# TS-ARM3_0_5.net
KiCad netlist of a schematic drawn in EAGLE
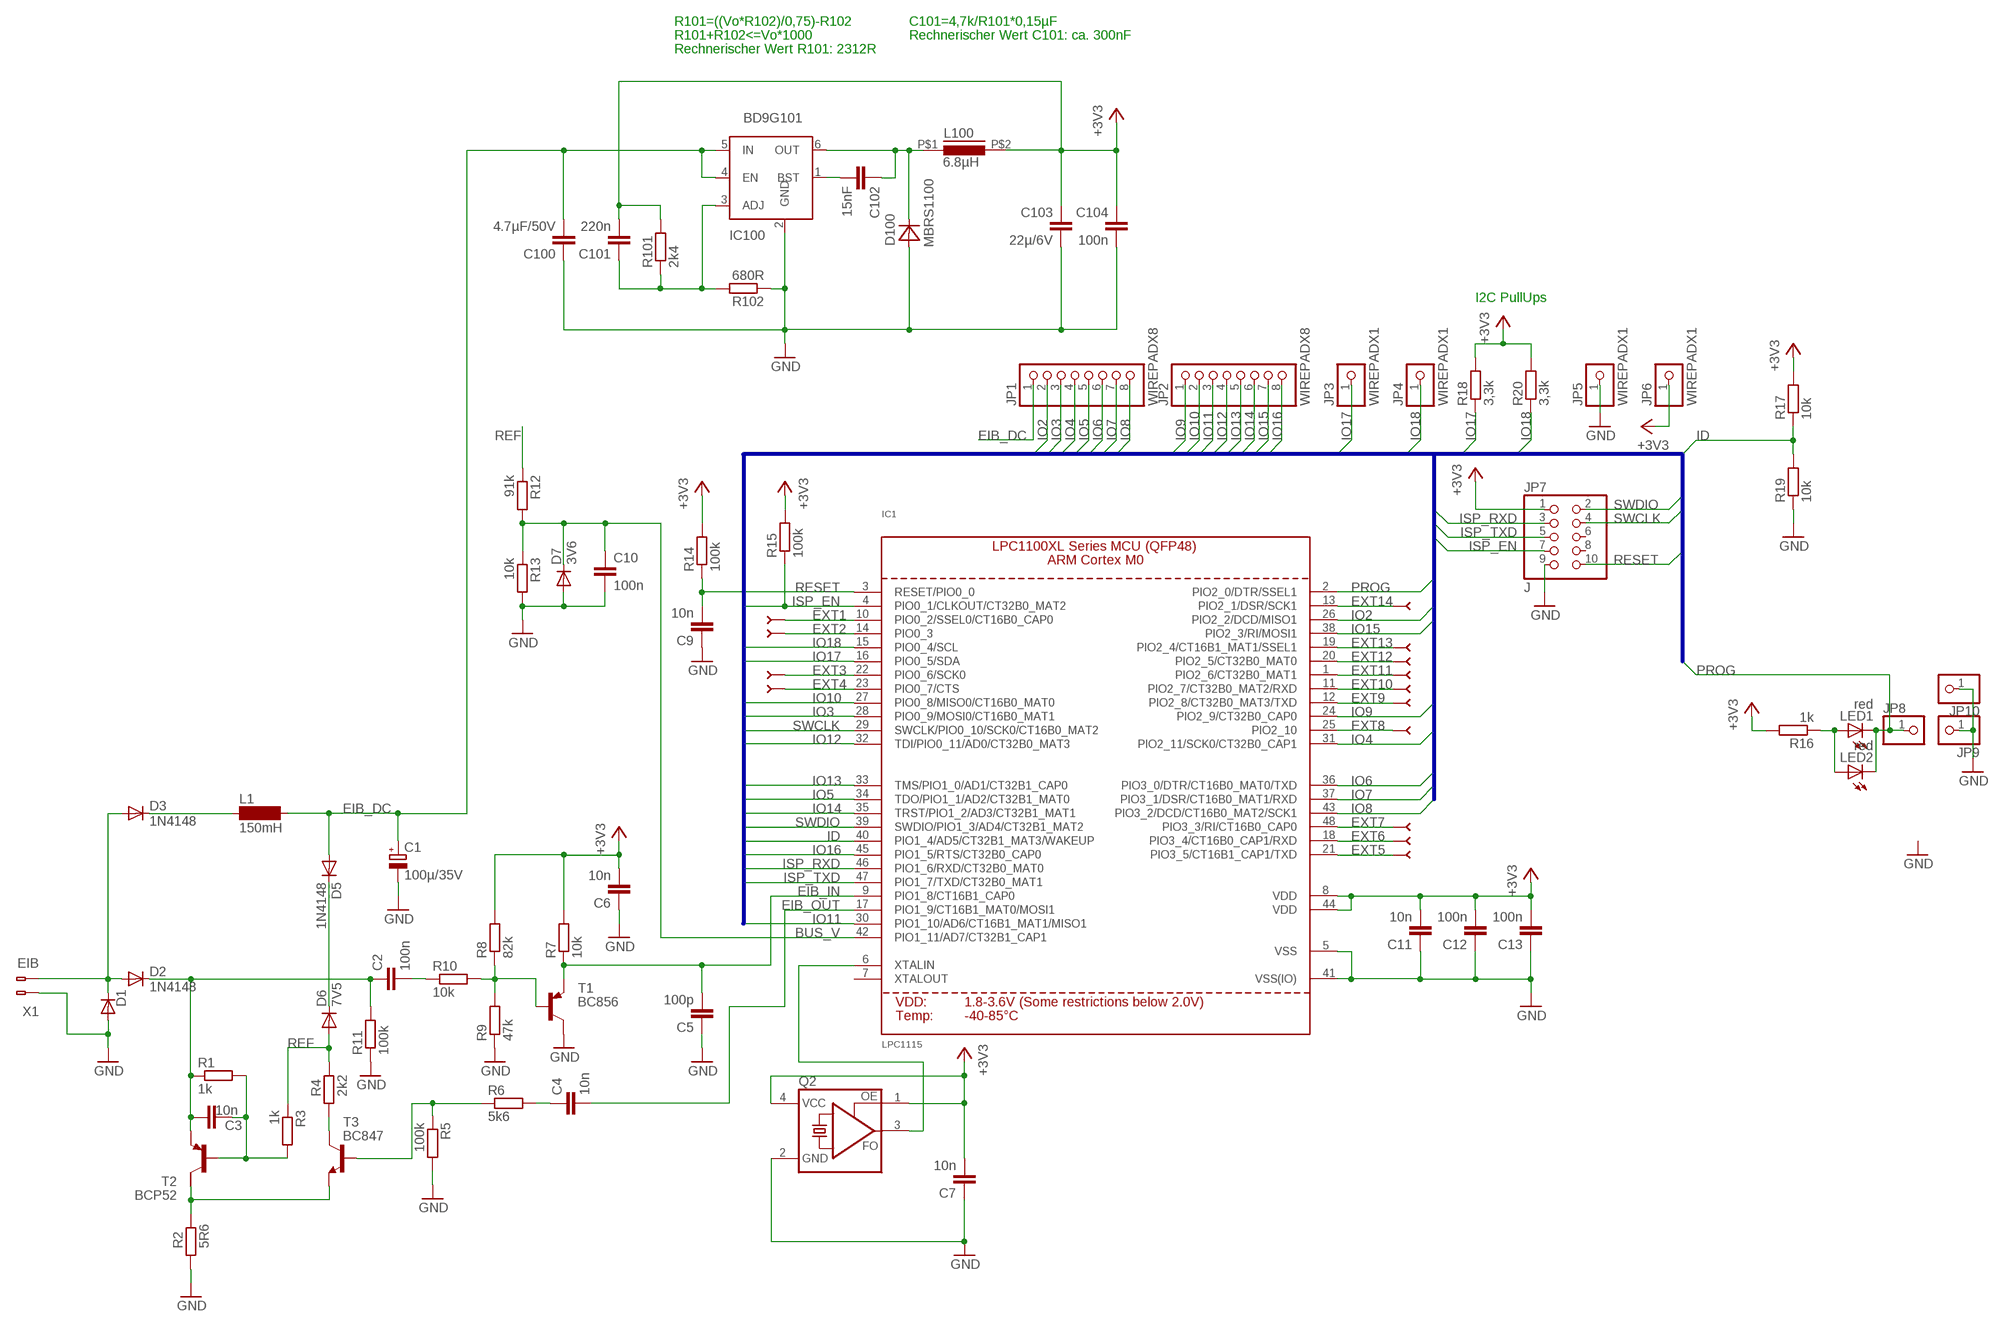
[diagram p0: schematic, sheet 1]

(export (version "E")
  (design (tool "Eeschema 10.0.6"))
  (components
    (comp (ref "C1")
      (value "100µ/35V")
      (footprint "eagle-import:SANYO-OSCON_SMD_C6")
      (libsource (lib "eagle-import") (part "CPOL-EUSANYO_SMD_C6"))
    )
    (comp (ref "C2")
      (value "100n")
      (footprint "eagle-import:C1206")
      (libsource (lib "eagle-import") (part "C-EUC1206"))
    )
    (comp (ref "C3")
      (value "10n")
      (footprint "eagle-import:C1206")
      (libsource (lib "eagle-import") (part "C-EUC1206"))
    )
    (comp (ref "C4")
      (value "10n")
      (footprint "eagle-import:C1206")
      (libsource (lib "eagle-import") (part "C-EUC1206"))
    )
    (comp (ref "C5")
      (value "100p")
      (footprint "eagle-import:C1206")
      (libsource (lib "eagle-import") (part "C-EUC1206"))
    )
    (comp (ref "C6")
      (value "10n")
      (footprint "eagle-import:C1206")
      (libsource (lib "eagle-import") (part "C-EUC1206"))
    )
    (comp (ref "C7")
      (value "10n")
      (footprint "eagle-import:C1206")
      (libsource (lib "eagle-import") (part "C-EUC1206"))
    )
    (comp (ref "C9")
      (value "10n")
      (footprint "eagle-import:C1206")
      (libsource (lib "eagle-import") (part "C-EUC1206"))
    )
    (comp (ref "C10")
      (value "100n")
      (footprint "eagle-import:C1206")
      (libsource (lib "eagle-import") (part "C-EUC1206"))
    )
    (comp (ref "C11")
      (value "10n")
      (footprint "eagle-import:C1206")
      (libsource (lib "eagle-import") (part "C-EUC1206"))
    )
    (comp (ref "C12")
      (value "100n")
      (footprint "eagle-import:C1206")
      (libsource (lib "eagle-import") (part "C-EUC1206"))
    )
    (comp (ref "C13")
      (value "100n")
      (footprint "eagle-import:C1206")
      (libsource (lib "eagle-import") (part "C-EUC1206"))
    )
    (comp (ref "C100")
      (value "4.7µF/50V")
      (footprint "eagle-import:C1206")
      (libsource (lib "eagle-import") (part "C-EUC1206"))
    )
    (comp (ref "C101")
      (value "220n")
      (footprint "eagle-import:C1206")
      (libsource (lib "eagle-import") (part "C-EUC1206"))
    )
    (comp (ref "C102")
      (value "15nF")
      (footprint "eagle-import:C1206")
      (libsource (lib "eagle-import") (part "C-EUC1206"))
    )
    (comp (ref "C103")
      (value "22µ/6V")
      (footprint "eagle-import:C1206")
      (libsource (lib "eagle-import") (part "C-EUC1206"))
    )
    (comp (ref "C104")
      (value "100n")
      (footprint "eagle-import:C1206")
      (libsource (lib "eagle-import") (part "C-EUC1206"))
    )
    (comp (ref "D1")
      (value "SMAJ40C")
      (footprint "eagle-import:SMB")
      (libsource (lib "eagle-import") (part "D-SMB"))
    )
    (comp (ref "D2")
      (value "1N4148")
      (footprint "eagle-import:MINIMELF")
      (libsource (lib "eagle-import") (part "DIODE-MINIMELF"))
    )
    (comp (ref "D3")
      (value "1N4148")
      (footprint "eagle-import:MINIMELF")
      (libsource (lib "eagle-import") (part "DIODE-MINIMELF"))
    )
    (comp (ref "D5")
      (value "1N4148")
      (footprint "eagle-import:MINIMELF")
      (libsource (lib "eagle-import") (part "DIODE-MINIMELF"))
    )
    (comp (ref "D6")
      (value "7V5")
      (footprint "eagle-import:MINIMELF")
      (libsource (lib "eagle-import") (part "DIODE-MINIMELF"))
    )
    (comp (ref "D7")
      (value "3V6")
      (footprint "eagle-import:MINIMELF")
      (libsource (lib "eagle-import") (part "DIODE-MINIMELF"))
    )
    (comp (ref "D100")
      (value "MBRS1100")
      (footprint "eagle-import:SMA")
      (libsource (lib "eagle-import") (part "MBRA340T3"))
    )
    (comp (ref "IC1")
      (value "LPC1115")
      (footprint "eagle-import:LQFP48")
      (libsource (lib "eagle-import") (part "LPC1113/4/5_QFP48_XLSERIES"))
    )
    (comp (ref "IC100")
      (value "BD9G101")
      (footprint "eagle-import:SOT23-6")
      (libsource (lib "eagle-import") (part "BD9G101GBD9G101G-SOT23-6"))
    )
    (comp (ref "JP1")
      (value "WIREPADX8")
      (footprint "eagle-import:SMD1,27X2,54X8")
      (libsource (lib "eagle-import") (part "WIREPADX8"))
    )
    (comp (ref "JP2")
      (value "WIREPADX8")
      (footprint "eagle-import:SMD1,27X2,54X8")
      (libsource (lib "eagle-import") (part "WIREPADX8"))
    )
    (comp (ref "JP3")
      (value "WIREPADX1")
      (footprint "eagle-import:SMD1,27X2,54")
      (libsource (lib "eagle-import") (part "WIREPADX1"))
    )
    (comp (ref "JP4")
      (value "WIREPADX1")
      (footprint "eagle-import:SMD1,27X2,54")
      (libsource (lib "eagle-import") (part "WIREPADX1"))
    )
    (comp (ref "JP5")
      (value "WIREPADX1")
      (footprint "eagle-import:SMD1,27X2,54")
      (libsource (lib "eagle-import") (part "WIREPADX1"))
    )
    (comp (ref "JP6")
      (value "WIREPADX1")
      (footprint "eagle-import:SMD1,27X2,54")
      (libsource (lib "eagle-import") (part "WIREPADX1"))
    )
    (comp (ref "JP7")
      (value "J")
      (footprint "eagle-import:2X05M")
      (libsource (lib "eagle-import") (part "PINHD-2X05_2.00"))
    )
    (comp (ref "JP8")
      (value "PINHD-1X1")
      (footprint "eagle-import:1X01")
      (libsource (lib "eagle-import") (part "PINHD-1X1"))
    )
    (comp (ref "JP9")
      (value "PINHD-1X1")
      (footprint "eagle-import:1X01")
      (libsource (lib "eagle-import") (part "PINHD-1X1"))
    )
    (comp (ref "JP10")
      (value "PINHD-1X1")
      (footprint "eagle-import:1X01")
      (libsource (lib "eagle-import") (part "PINHD-1X1"))
    )
    (comp (ref "L1")
      (value "150mH")
      (footprint "eagle-import:SD12_1000")
      (libsource (lib "eagle-import") (part "SD12-1000"))
    )
    (comp (ref "L100")
      (value "6.8µH")
      (footprint "eagle-import:PIS2812")
      (libsource (lib "eagle-import") (part "IND_FASTRON_1616FPS"))
    )
    (comp (ref "LED1")
      (value "red")
      (footprint "eagle-import:CHIPLED_1206")
      (libsource (lib "eagle-import") (part "LEDCHIPLED_1206"))
    )
    (comp (ref "LED2")
      (value "red")
      (footprint "eagle-import:LED3MM")
      (libsource (lib "eagle-import") (part "LED3MM"))
    )
    (comp (ref "P1")
      (value "PAD")
      (footprint "eagle-import:PAD")
      (libsource (lib "eagle-import") (part "PAD"))
    )
    (comp (ref "P2")
      (value "PAD")
      (footprint "eagle-import:PAD")
      (libsource (lib "eagle-import") (part "PAD"))
    )
    (comp (ref "P3")
      (value "PAD")
      (footprint "eagle-import:PAD")
      (libsource (lib "eagle-import") (part "PAD"))
    )
    (comp (ref "P4")
      (value "PAD")
      (footprint "eagle-import:PAD")
      (libsource (lib "eagle-import") (part "PAD"))
    )
    (comp (ref "P5")
      (value "PAD")
      (footprint "eagle-import:PAD")
      (libsource (lib "eagle-import") (part "PAD"))
    )
    (comp (ref "P6")
      (value "PAD")
      (footprint "eagle-import:PAD")
      (libsource (lib "eagle-import") (part "PAD"))
    )
    (comp (ref "P7")
      (value "PAD")
      (footprint "eagle-import:PAD")
      (libsource (lib "eagle-import") (part "PAD"))
    )
    (comp (ref "P8")
      (value "PAD")
      (footprint "eagle-import:PAD")
      (libsource (lib "eagle-import") (part "PAD"))
    )
    (comp (ref "P9")
      (value "PAD")
      (footprint "eagle-import:PAD")
      (libsource (lib "eagle-import") (part "PAD"))
    )
    (comp (ref "P10")
      (value "PAD")
      (footprint "eagle-import:PAD")
      (libsource (lib "eagle-import") (part "PAD"))
    )
    (comp (ref "P11")
      (value "PAD")
      (footprint "eagle-import:PAD")
      (libsource (lib "eagle-import") (part "PAD"))
    )
    (comp (ref "P12")
      (value "PAD")
      (footprint "eagle-import:PAD")
      (libsource (lib "eagle-import") (part "PAD"))
    )
    (comp (ref "P13")
      (value "PAD")
      (footprint "eagle-import:PAD")
      (libsource (lib "eagle-import") (part "PAD"))
    )
    (comp (ref "P14")
      (value "PAD")
      (footprint "eagle-import:PAD")
      (libsource (lib "eagle-import") (part "PAD"))
    )
    (comp (ref "Q2")
      (value "ASFL")
      (footprint "eagle-import:ASF")
      (libsource (lib "eagle-import") (part "ASFL"))
    )
    (comp (ref "R1")
      (value "1k")
      (footprint "eagle-import:R1206")
      (libsource (lib "eagle-import") (part "R-EU_R1206"))
    )
    (comp (ref "R2")
      (value "5R6")
      (footprint "eagle-import:R1206")
      (libsource (lib "eagle-import") (part "R-EU_R1206"))
    )
    (comp (ref "R3")
      (value "1k")
      (footprint "eagle-import:R1206")
      (libsource (lib "eagle-import") (part "R-EU_R1206"))
    )
    (comp (ref "R4")
      (value "2k2")
      (footprint "eagle-import:R1206")
      (libsource (lib "eagle-import") (part "R-EU_R1206"))
    )
    (comp (ref "R5")
      (value "100k")
      (footprint "eagle-import:R1206")
      (libsource (lib "eagle-import") (part "R-EU_R1206"))
    )
    (comp (ref "R6")
      (value "5k6")
      (footprint "eagle-import:R1206")
      (libsource (lib "eagle-import") (part "R-EU_R1206"))
    )
    (comp (ref "R7")
      (value "10k")
      (footprint "eagle-import:R1206")
      (libsource (lib "eagle-import") (part "R-EU_R1206"))
    )
    (comp (ref "R8")
      (value "82k")
      (footprint "eagle-import:R1206")
      (libsource (lib "eagle-import") (part "R-EU_R1206"))
    )
    (comp (ref "R9")
      (value "47k")
      (footprint "eagle-import:R1206")
      (libsource (lib "eagle-import") (part "R-EU_R1206"))
    )
    (comp (ref "R10")
      (value "10k")
      (footprint "eagle-import:R1206")
      (libsource (lib "eagle-import") (part "R-EU_R1206"))
    )
    (comp (ref "R11")
      (value "100k")
      (footprint "eagle-import:R1206")
      (libsource (lib "eagle-import") (part "R-EU_R1206"))
    )
    (comp (ref "R12")
      (value "91k")
      (footprint "eagle-import:R1206")
      (libsource (lib "eagle-import") (part "R-EU_R1206"))
    )
    (comp (ref "R13")
      (value "10k")
      (footprint "eagle-import:R1206")
      (libsource (lib "eagle-import") (part "R-EU_R1206"))
    )
    (comp (ref "R14")
      (value "100k")
      (footprint "eagle-import:R1206")
      (libsource (lib "eagle-import") (part "R-EU_R1206"))
    )
    (comp (ref "R15")
      (value "100k")
      (footprint "eagle-import:R1206")
      (libsource (lib "eagle-import") (part "R-EU_R1206"))
    )
    (comp (ref "R16")
      (value "1k")
      (footprint "eagle-import:R1206")
      (libsource (lib "eagle-import") (part "R-EU_R1206"))
    )
    (comp (ref "R17")
      (value "10k")
      (footprint "eagle-import:R1206")
      (libsource (lib "eagle-import") (part "R-EU_R1206"))
    )
    (comp (ref "R18")
      (value "3,3k")
      (footprint "eagle-import:R1206")
      (libsource (lib "eagle-import") (part "R-EU_R1206"))
    )
    (comp (ref "R19")
      (value "10k")
      (footprint "eagle-import:R1206")
      (libsource (lib "eagle-import") (part "R-EU_R1206"))
    )
    (comp (ref "R20")
      (value "3,3k")
      (footprint "eagle-import:R1206")
      (libsource (lib "eagle-import") (part "R-EU_R1206"))
    )
    (comp (ref "R101")
      (value "2k4")
      (footprint "eagle-import:R1206")
      (libsource (lib "eagle-import") (part "R-EU_R1206"))
    )
    (comp (ref "R102")
      (value "680R")
      (footprint "eagle-import:R1206")
      (libsource (lib "eagle-import") (part "R-EU_R1206"))
    )
    (comp (ref "T1")
      (value "BC856")
      (footprint "eagle-import:SOT23-BEC")
      (libsource (lib "eagle-import") (part "BC856SMDB"))
    )
    (comp (ref "T2")
      (value "BCP52")
      (footprint "eagle-import:SOT223")
      (libsource (lib "eagle-import") (part "FZT753SMD"))
    )
    (comp (ref "T3")
      (value "BC847")
      (footprint "eagle-import:SOT23")
      (libsource (lib "eagle-import") (part "BC847"))
    )
    (comp (ref "X1")
      (value "EIB")
      (footprint "eagle-import:BUSKLEMME243-724")
      (libsource (lib "eagle-import") (part "EIB"))
    )
  )
  (nets
    (net (code "1") (name "+3V3") (class "Default")
      (node (ref "C101") (pin "2") (pinfunction "2_2") (pintype "passive"))
      (node (ref "C103") (pin "1") (pinfunction "1_1") (pintype "passive"))
      (node (ref "C104") (pin "1") (pinfunction "1_1") (pintype "passive"))
      (node (ref "C11") (pin "2") (pinfunction "2_2") (pintype "passive"))
      (node (ref "C12") (pin "2") (pinfunction "2_2") (pintype "passive"))
      (node (ref "C13") (pin "2") (pinfunction "2_2") (pintype "passive"))
      (node (ref "C6") (pin "2") (pinfunction "2_2") (pintype "passive"))
      (node (ref "C7") (pin "2") (pinfunction "2_2") (pintype "passive"))
      (node (ref "IC1") (pin "44") (pinfunction "VDD_44") (pintype "power_in"))
      (node (ref "IC1") (pin "8") (pinfunction "VDD_8") (pintype "power_in"))
      (node (ref "JP6") (pin "1") (pinfunction "1_1") (pintype "passive"))
      (node (ref "JP7") (pin "1") (pinfunction "1_1") (pintype "passive"))
      (node (ref "L100") (pin "P$2") (pinfunction "2_P$2") (pintype "passive"))
      (node (ref "Q2") (pin "1") (pinfunction "OE_1") (pintype "input"))
      (node (ref "Q2") (pin "4") (pinfunction "VCC_4") (pintype "power_in"))
      (node (ref "R101") (pin "2") (pinfunction "2_2") (pintype "passive"))
      (node (ref "R14") (pin "2") (pinfunction "2_2") (pintype "passive"))
      (node (ref "R15") (pin "2") (pinfunction "2_2") (pintype "passive"))
      (node (ref "R16") (pin "2") (pinfunction "2_2") (pintype "passive"))
      (node (ref "R17") (pin "2") (pinfunction "2_2") (pintype "passive"))
      (node (ref "R18") (pin "2") (pinfunction "2_2") (pintype "passive"))
      (node (ref "R20") (pin "2") (pinfunction "2_2") (pintype "passive"))
      (node (ref "R7") (pin "2") (pinfunction "2_2") (pintype "passive"))
      (node (ref "R8") (pin "2") (pinfunction "2_2") (pintype "passive"))
    )
    (net (code "2") (name "/BUS_V") (class "Default")
      (node (ref "C10") (pin "2") (pinfunction "2_2") (pintype "passive"))
      (node (ref "D7") (pin "C") (pinfunction "C_C") (pintype "passive"))
      (node (ref "IC1") (pin "42") (pinfunction "PIO1_11/AD7/CT32B1_CAP1_42") (pintype "bidirectional"))
      (node (ref "R12") (pin "2") (pinfunction "2_2") (pintype "passive"))
      (node (ref "R13") (pin "1") (pinfunction "1_1") (pintype "passive"))
    )
    (net (code "3") (name "/EIB_DC") (class "Default")
      (node (ref "C1") (pin "+") (pinfunction "+_+") (pintype "passive"))
      (node (ref "C100") (pin "2") (pinfunction "2_2") (pintype "passive"))
      (node (ref "D5") (pin "A") (pinfunction "A_A") (pintype "passive"))
      (node (ref "IC100") (pin "4") (pinfunction "EN_4") (pintype "input"))
      (node (ref "IC100") (pin "5") (pinfunction "IN_5") (pintype "input"))
      (node (ref "JP1") (pin "1") (pinfunction "1_1") (pintype "passive"))
      (node (ref "L1") (pin "2") (pinfunction "2_2") (pintype "passive"))
    )
    (net (code "4") (name "/EIB_IN") (class "Default")
      (node (ref "C5") (pin "2") (pinfunction "2_2") (pintype "passive"))
      (node (ref "IC1") (pin "9") (pinfunction "PIO1_8/CT16B1_CAP0_9") (pintype "bidirectional"))
      (node (ref "R7") (pin "1") (pinfunction "1_1") (pintype "passive"))
      (node (ref "T1") (pin "E") (pinfunction "E_E") (pintype "passive"))
    )
    (net (code "5") (name "/EIB_OUT") (class "Default")
      (node (ref "C4") (pin "2") (pinfunction "2_2") (pintype "passive"))
      (node (ref "IC1") (pin "17") (pinfunction "PIO1_9/CT16B1_MAT0/MOSI1_17") (pintype "bidirectional"))
    )
    (net (code "6") (name "/EXT1") (class "Default")
      (node (ref "IC1") (pin "10") (pinfunction "PIO0_2/SSEL0/CT16B0_CAP0_10") (pintype "bidirectional"))
      (node (ref "P1") (pin "1") (pinfunction "1_1") (pintype "bidirectional"))
    )
    (net (code "7") (name "/EXT2") (class "Default")
      (node (ref "IC1") (pin "14") (pinfunction "PIO0_3_14") (pintype "bidirectional"))
      (node (ref "P2") (pin "1") (pinfunction "1_1") (pintype "bidirectional"))
    )
    (net (code "8") (name "/EXT3") (class "Default")
      (node (ref "IC1") (pin "22") (pinfunction "PIO0_6/SCK0_22") (pintype "bidirectional"))
      (node (ref "P13") (pin "1") (pinfunction "1_1") (pintype "bidirectional"))
    )
    (net (code "9") (name "/EXT4") (class "Default")
      (node (ref "IC1") (pin "23") (pinfunction "PIO0_7/CTS_23") (pintype "bidirectional"))
      (node (ref "P14") (pin "1") (pinfunction "1_1") (pintype "bidirectional"))
    )
    (net (code "10") (name "/EXT5") (class "Default")
      (node (ref "IC1") (pin "21") (pinfunction "PIO3_5/CT16B1_CAP1/TXD_21") (pintype "bidirectional"))
      (node (ref "P12") (pin "1") (pinfunction "1_1") (pintype "bidirectional"))
    )
    (net (code "11") (name "/EXT6") (class "Default")
      (node (ref "IC1") (pin "18") (pinfunction "PIO3_4/CT16B0_CAP1/RXD_18") (pintype "bidirectional"))
      (node (ref "P11") (pin "1") (pinfunction "1_1") (pintype "bidirectional"))
    )
    (net (code "12") (name "/EXT7") (class "Default")
      (node (ref "IC1") (pin "48") (pinfunction "PIO3_3/RI/CT16B0_CAP0_48") (pintype "bidirectional"))
      (node (ref "P10") (pin "1") (pinfunction "1_1") (pintype "bidirectional"))
    )
    (net (code "13") (name "/EXT8") (class "Default")
      (node (ref "IC1") (pin "25") (pinfunction "PIO2_10_25") (pintype "bidirectional"))
      (node (ref "P6") (pin "1") (pinfunction "1_1") (pintype "bidirectional"))
    )
    (net (code "14") (name "/EXT9") (class "Default")
      (node (ref "IC1") (pin "12") (pinfunction "PIO2_8/CT32B0_MAT3/TXD_12") (pintype "bidirectional"))
      (node (ref "P4") (pin "1") (pinfunction "1_1") (pintype "bidirectional"))
    )
    (net (code "15") (name "/EXT10") (class "Default")
      (node (ref "IC1") (pin "11") (pinfunction "PIO2_7/CT32B0_MAT2/RXD_11") (pintype "bidirectional"))
      (node (ref "P5") (pin "1") (pinfunction "1_1") (pintype "bidirectional"))
    )
    (net (code "16") (name "/EXT11") (class "Default")
      (node (ref "IC1") (pin "1") (pinfunction "PIO2_6/CT32B0_MAT1_1") (pintype "bidirectional"))
      (node (ref "P9") (pin "1") (pinfunction "1_1") (pintype "bidirectional"))
    )
    (net (code "17") (name "/EXT12") (class "Default")
      (node (ref "IC1") (pin "20") (pinfunction "PIO2_5/CT32B0_MAT0_20") (pintype "bidirectional"))
      (node (ref "P8") (pin "1") (pinfunction "1_1") (pintype "bidirectional"))
    )
    (net (code "18") (name "/EXT13") (class "Default")
      (node (ref "IC1") (pin "19") (pinfunction "PIO2_4/CT16B1_MAT1/SSEL1_19") (pintype "bidirectional"))
      (node (ref "P7") (pin "1") (pinfunction "1_1") (pintype "bidirectional"))
    )
    (net (code "19") (name "/EXT14") (class "Default")
      (node (ref "IC1") (pin "13") (pinfunction "PIO2_1/DSR/SCK1_13") (pintype "bidirectional"))
      (node (ref "P3") (pin "1") (pinfunction "1_1") (pintype "bidirectional"))
    )
    (net (code "20") (name "/ID") (class "Default")
      (node (ref "IC1") (pin "40") (pinfunction "PIO1_4/AD5/CT32B1_MAT3/WAKEUP_40") (pintype "bidirectional"))
      (node (ref "R17") (pin "1") (pinfunction "1_1") (pintype "passive"))
      (node (ref "R19") (pin "2") (pinfunction "2_2") (pintype "passive"))
    )
    (net (code "21") (name "/IO2") (class "Default")
      (node (ref "IC1") (pin "26") (pinfunction "PIO2_2/DCD/MISO1_26") (pintype "bidirectional"))
      (node (ref "JP1") (pin "2") (pinfunction "2_2") (pintype "passive"))
    )
    (net (code "22") (name "/IO3") (class "Default")
      (node (ref "IC1") (pin "28") (pinfunction "PIO0_9/MOSI0/CT16B0_MAT1_28") (pintype "bidirectional"))
      (node (ref "JP1") (pin "3") (pinfunction "3_3") (pintype "passive"))
    )
    (net (code "23") (name "/IO4") (class "Default")
      (node (ref "IC1") (pin "31") (pinfunction "PIO2_11/SCK0/CT32B0_CAP1_31") (pintype "bidirectional"))
      (node (ref "JP1") (pin "4") (pinfunction "4_4") (pintype "passive"))
    )
    (net (code "24") (name "/IO5") (class "Default")
      (node (ref "IC1") (pin "34") (pinfunction "TDO/PIO1_1/AD2/CT32B1_MAT0_34") (pintype "bidirectional"))
      (node (ref "JP1") (pin "5") (pinfunction "5_5") (pintype "passive"))
    )
    (net (code "25") (name "/IO6") (class "Default")
      (node (ref "IC1") (pin "36") (pinfunction "PIO3_0/DTR/CT16B0_MAT0/TXD_36") (pintype "bidirectional"))
      (node (ref "JP1") (pin "6") (pinfunction "6_6") (pintype "passive"))
    )
    (net (code "26") (name "/IO7") (class "Default")
      (node (ref "IC1") (pin "37") (pinfunction "PIO3_1/DSR/CT16B0_MAT1/RXD_37") (pintype "bidirectional"))
      (node (ref "JP1") (pin "7") (pinfunction "7_7") (pintype "passive"))
    )
    (net (code "27") (name "/IO8") (class "Default")
      (node (ref "IC1") (pin "43") (pinfunction "PIO3_2/DCD/CT16B0_MAT2/SCK1_43") (pintype "bidirectional"))
      (node (ref "JP1") (pin "8") (pinfunction "8_8") (pintype "passive"))
    )
    (net (code "28") (name "/IO9") (class "Default")
      (node (ref "IC1") (pin "24") (pinfunction "PIO2_9/CT32B0_CAP0_24") (pintype "bidirectional"))
      (node (ref "JP2") (pin "1") (pinfunction "1_1") (pintype "passive"))
    )
    (net (code "29") (name "/IO10") (class "Default")
      (node (ref "IC1") (pin "27") (pinfunction "PIO0_8/MISO0/CT16B0_MAT0_27") (pintype "bidirectional"))
      (node (ref "JP2") (pin "2") (pinfunction "2_2") (pintype "passive"))
    )
    (net (code "30") (name "/IO11") (class "Default")
      (node (ref "IC1") (pin "30") (pinfunction "PIO1_10/AD6/CT16B1_MAT1/MISO1_30") (pintype "bidirectional"))
      (node (ref "JP2") (pin "3") (pinfunction "3_3") (pintype "passive"))
    )
    (net (code "31") (name "/IO12") (class "Default")
      (node (ref "IC1") (pin "32") (pinfunction "TDI/PIO0_11/AD0/CT32B0_MAT3_32") (pintype "bidirectional"))
      (node (ref "JP2") (pin "4") (pinfunction "4_4") (pintype "passive"))
    )
    (net (code "32") (name "/IO13") (class "Default")
      (node (ref "IC1") (pin "33") (pinfunction "TMS/PIO1_0/AD1/CT32B1_CAP0_33") (pintype "bidirectional"))
      (node (ref "JP2") (pin "5") (pinfunction "5_5") (pintype "passive"))
    )
    (net (code "33") (name "/IO14") (class "Default")
      (node (ref "IC1") (pin "35") (pinfunction "TRST/PIO1_2/AD3/CT32B1_MAT1_35") (pintype "bidirectional"))
      (node (ref "JP2") (pin "6") (pinfunction "6_6") (pintype "passive"))
    )
    (net (code "34") (name "/IO15") (class "Default")
      (node (ref "IC1") (pin "38") (pinfunction "PIO2_3/RI/MOSI1_38") (pintype "bidirectional"))
      (node (ref "JP2") (pin "7") (pinfunction "7_7") (pintype "passive"))
    )
    (net (code "35") (name "/IO16") (class "Default")
      (node (ref "IC1") (pin "45") (pinfunction "PIO1_5/RTS/CT32B0_CAP0_45") (pintype "bidirectional"))
      (node (ref "JP2") (pin "8") (pinfunction "8_8") (pintype "passive"))
    )
    (net (code "36") (name "/IO17") (class "Default")
      (node (ref "IC1") (pin "16") (pinfunction "PIO0_5/SDA_16") (pintype "bidirectional"))
      (node (ref "JP3") (pin "1") (pinfunction "1_1") (pintype "passive"))
      (node (ref "R18") (pin "1") (pinfunction "1_1") (pintype "passive"))
    )
    (net (code "37") (name "/IO18") (class "Default")
      (node (ref "IC1") (pin "15") (pinfunction "PIO0_4/SCL_15") (pintype "bidirectional"))
      (node (ref "JP4") (pin "1") (pinfunction "1_1") (pintype "passive"))
      (node (ref "R20") (pin "1") (pinfunction "1_1") (pintype "passive"))
    )
    (net (code "38") (name "/ISP_EN") (class "Default")
      (node (ref "IC1") (pin "4") (pinfunction "PIO0_1/CLKOUT/CT32B0_MAT2_4") (pintype "bidirectional"))
      (node (ref "JP7") (pin "7") (pinfunction "7_7") (pintype "passive"))
      (node (ref "R15") (pin "1") (pinfunction "1_1") (pintype "passive"))
    )
    (net (code "39") (name "/ISP_RXD") (class "Default")
      (node (ref "IC1") (pin "46") (pinfunction "PIO1_6/RXD/CT32B0_MAT0_46") (pintype "bidirectional"))
      (node (ref "JP7") (pin "3") (pinfunction "3_3") (pintype "passive"))
    )
    (net (code "40") (name "/ISP_TXD") (class "Default")
      (node (ref "IC1") (pin "47") (pinfunction "PIO1_7/TXD/CT32B0_MAT1_47") (pintype "bidirectional"))
      (node (ref "JP7") (pin "5") (pinfunction "5_5") (pintype "passive"))
    )
    (net (code "41") (name "/PROG") (class "Default")
      (node (ref "IC1") (pin "2") (pinfunction "PIO2_0/DTR/SSEL1_2") (pintype "bidirectional"))
      (node (ref "JP8") (pin "1") (pinfunction "1_1") (pintype "passive"))
      (node (ref "LED1") (pin "C") (pinfunction "C_C") (pintype "passive"))
      (node (ref "LED2") (pin "K") (pinfunction "C_K") (pintype "passive"))
    )
    (net (code "42") (name "/REF") (class "Default")
      (node (ref "D6") (pin "A") (pinfunction "A_A") (pintype "passive"))
      (node (ref "R12") (pin "1") (pinfunction "1_1") (pintype "passive"))
      (node (ref "R3") (pin "1") (pinfunction "1_1") (pintype "passive"))
      (node (ref "R4") (pin "2") (pinfunction "2_2") (pintype "passive"))
    )
    (net (code "43") (name "/RESET") (class "Default")
      (node (ref "C9") (pin "2") (pinfunction "2_2") (pintype "passive"))
      (node (ref "IC1") (pin "3") (pinfunction "RESET/PIO0_0_3") (pintype "bidirectional"))
      (node (ref "JP7") (pin "10") (pinfunction "10_10") (pintype "passive"))
      (node (ref "R14") (pin "1") (pinfunction "1_1") (pintype "passive"))
    )
    (net (code "44") (name "/SWCLK") (class "Default")
      (node (ref "IC1") (pin "29") (pinfunction "SWCLK/PIO0_10/SCK0/CT16B0_MAT2_29") (pintype "bidirectional"))
      (node (ref "JP7") (pin "4") (pinfunction "4_4") (pintype "passive"))
    )
    (net (code "45") (name "/SWDIO") (class "Default")
      (node (ref "IC1") (pin "39") (pinfunction "SWDIO/PIO1_3/AD4/CT32B1_MAT2_39") (pintype "bidirectional"))
      (node (ref "JP7") (pin "2") (pinfunction "2_2") (pintype "passive"))
    )
    (net (code "46") (name "GND") (class "Default")
      (node (ref "C1") (pin "-") (pinfunction "-_-") (pintype "passive"))
      (node (ref "C10") (pin "1") (pinfunction "1_1") (pintype "passive"))
      (node (ref "C100") (pin "1") (pinfunction "1_1") (pintype "passive"))
      (node (ref "C103") (pin "2") (pinfunction "2_2") (pintype "passive"))
      (node (ref "C104") (pin "2") (pinfunction "2_2") (pintype "passive"))
      (node (ref "C11") (pin "1") (pinfunction "1_1") (pintype "passive"))
      (node (ref "C12") (pin "1") (pinfunction "1_1") (pintype "passive"))
      (node (ref "C13") (pin "1") (pinfunction "1_1") (pintype "passive"))
      (node (ref "C5") (pin "1") (pinfunction "1_1") (pintype "passive"))
      (node (ref "C6") (pin "1") (pinfunction "1_1") (pintype "passive"))
      (node (ref "C7") (pin "1") (pinfunction "1_1") (pintype "passive"))
      (node (ref "C9") (pin "1") (pinfunction "1_1") (pintype "passive"))
      (node (ref "D1") (pin "2") (pinfunction "A_2") (pintype "passive"))
      (node (ref "D100") (pin "A") (pinfunction "A_A") (pintype "passive"))
      (node (ref "D7") (pin "A") (pinfunction "A_A") (pintype "passive"))
      (node (ref "IC1") (pin "41") (pinfunction "VSS(IO)_41") (pintype "power_in"))
      (node (ref "IC1") (pin "5") (pinfunction "VSS_5") (pintype "power_in"))
      (node (ref "IC100") (pin "2") (pinfunction "GND_2") (pintype "power_in"))
      (node (ref "JP10") (pin "1") (pinfunction "1_1") (pintype "passive"))
      (node (ref "JP5") (pin "1") (pinfunction "1_1") (pintype "passive"))
      (node (ref "JP7") (pin "9") (pinfunction "9_9") (pintype "passive"))
      (node (ref "JP9") (pin "1") (pinfunction "1_1") (pintype "passive"))
      (node (ref "Q2") (pin "2") (pinfunction "GND_2") (pintype "power_in"))
      (node (ref "R102") (pin "1") (pinfunction "1_1") (pintype "passive"))
      (node (ref "R11") (pin "1") (pinfunction "1_1") (pintype "passive"))
      (node (ref "R13") (pin "2") (pinfunction "2_2") (pintype "passive"))
      (node (ref "R19") (pin "1") (pinfunction "1_1") (pintype "passive"))
      (node (ref "R2") (pin "1") (pinfunction "1_1") (pintype "passive"))
      (node (ref "R5") (pin "2") (pinfunction "2_2") (pintype "passive"))
      (node (ref "R9") (pin "1") (pinfunction "1_1") (pintype "passive"))
      (node (ref "T1") (pin "C") (pinfunction "C_C") (pintype "passive"))
      (node (ref "X1") (pin "1") (pinfunction "B-1_1") (pintype "passive"))
    )
    (net (code "47") (name "Net-(C2-Pad2)") (class "Default")
      (node (ref "C2") (pin "2") (pinfunction "2_2") (pintype "passive"))
      (node (ref "R10") (pin "1") (pinfunction "1_1") (pintype "passive"))
    )
    (net (code "48") (name "Net-(C4-Pad1)") (class "Default")
      (node (ref "C4") (pin "1") (pinfunction "1_1") (pintype "passive"))
      (node (ref "R6") (pin "2") (pinfunction "2_2") (pintype "passive"))
    )
    (net (code "49") (name "Net-(D1-C)") (class "Default")
      (node (ref "D1") (pin "1") (pinfunction "C_1") (pintype "passive"))
      (node (ref "D2") (pin "A") (pinfunction "A_A") (pintype "passive"))
      (node (ref "D3") (pin "A") (pinfunction "A_A") (pintype "passive"))
      (node (ref "X1") (pin "2") (pinfunction "B-2_2") (pintype "passive"))
    )
    (net (code "50") (name "Net-(D3-PadC)") (class "Default")
      (node (ref "D3") (pin "C") (pinfunction "C_C") (pintype "passive"))
      (node (ref "L1") (pin "1") (pinfunction "1_1") (pintype "passive"))
    )
    (net (code "51") (name "Net-(D5-PadC)") (class "Default")
      (node (ref "D5") (pin "C") (pinfunction "C_C") (pintype "passive"))
      (node (ref "D6") (pin "C") (pinfunction "C_C") (pintype "passive"))
    )
    (net (code "52") (name "Net-(IC1-XTALIN)") (class "Default")
      (node (ref "IC1") (pin "6") (pinfunction "XTALIN_6") (pintype "input"))
      (node (ref "Q2") (pin "3") (pinfunction "FO_3") (pintype "output"))
    )
    (net (code "53") (name "Net-(IC100-ADJ)") (class "Default")
      (node (ref "C101") (pin "1") (pinfunction "1_1") (pintype "passive"))
      (node (ref "IC100") (pin "3") (pinfunction "ADJ_3") (pintype "passive"))
      (node (ref "R101") (pin "1") (pinfunction "1_1") (pintype "passive"))
      (node (ref "R102") (pin "2") (pinfunction "2_2") (pintype "passive"))
    )
    (net (code "54") (name "Net-(IC100-BST)") (class "Default")
      (node (ref "C102") (pin "2") (pinfunction "2_2") (pintype "passive"))
      (node (ref "IC100") (pin "1") (pinfunction "BST_1") (pintype "output"))
    )
    (net (code "55") (name "Net-(IC100-OUT)") (class "Default")
      (node (ref "C102") (pin "1") (pinfunction "1_1") (pintype "passive"))
      (node (ref "D100") (pin "C") (pinfunction "C_C") (pintype "passive"))
      (node (ref "IC100") (pin "6") (pinfunction "OUT_6") (pintype "output"))
      (node (ref "L100") (pin "P$1") (pinfunction "1_P$1") (pintype "passive"))
    )
    (net (code "56") (name "Net-(LED1-PadA)") (class "Default")
      (node (ref "LED1") (pin "A") (pinfunction "A_A") (pintype "passive"))
      (node (ref "LED2") (pin "A") (pinfunction "A_A") (pintype "passive"))
      (node (ref "R16") (pin "1") (pinfunction "1_1") (pintype "passive"))
    )
    (net (code "57") (name "Net-(R10-Pad2)") (class "Default")
      (node (ref "R10") (pin "2") (pinfunction "2_2") (pintype "passive"))
      (node (ref "R8") (pin "1") (pinfunction "1_1") (pintype "passive"))
      (node (ref "R9") (pin "2") (pinfunction "2_2") (pintype "passive"))
      (node (ref "T1") (pin "B") (pinfunction "B_B") (pintype "passive"))
    )
    (net (code "58") (name "Net-(T2-B)") (class "Default")
      (node (ref "C3") (pin "2") (pinfunction "2_2") (pintype "passive"))
      (node (ref "R1") (pin "2") (pinfunction "2_2") (pintype "passive"))
      (node (ref "R3") (pin "2") (pinfunction "2_2") (pintype "passive"))
      (node (ref "T2") (pin "1") (pinfunction "B_1") (pintype "passive"))
    )
    (net (code "59") (name "Net-(T2-C)") (class "Default")
      (node (ref "R2") (pin "2") (pinfunction "2_2") (pintype "passive"))
      (node (ref "T2") (pin "2") (pinfunction "C_2") (pintype "passive"))
      (node (ref "T3") (pin "2") (pinfunction "E_2") (pintype "passive"))
    )
    (net (code "60") (name "Net-(T2-E)") (class "Default")
      (node (ref "C2") (pin "1") (pinfunction "1_1") (pintype "passive"))
      (node (ref "C3") (pin "1") (pinfunction "1_1") (pintype "passive"))
      (node (ref "D2") (pin "C") (pinfunction "C_C") (pintype "passive"))
      (node (ref "R1") (pin "1") (pinfunction "1_1") (pintype "passive"))
      (node (ref "R11") (pin "2") (pinfunction "2_2") (pintype "passive"))
      (node (ref "T2") (pin "3") (pinfunction "E_3") (pintype "passive"))
    )
    (net (code "61") (name "Net-(T3-B)") (class "Default")
      (node (ref "R5") (pin "1") (pinfunction "1_1") (pintype "passive"))
      (node (ref "R6") (pin "1") (pinfunction "1_1") (pintype "passive"))
      (node (ref "T3") (pin "1") (pinfunction "B_1") (pintype "passive"))
    )
    (net (code "62") (name "Net-(T3-C)") (class "Default")
      (node (ref "R4") (pin "1") (pinfunction "1_1") (pintype "passive"))
      (node (ref "T3") (pin "3") (pinfunction "C_3") (pintype "passive"))
    )
    (net (code "63") (name "unconnected-(IC1-XTALOUT-Pad7)") (class "Default")
      (node (ref "IC1") (pin "7") (pinfunction "XTALOUT_7") (pintype "output"))
    )
    (net (code "64") (name "unconnected-(JP7-Pad6)") (class "Default")
      (node (ref "JP7") (pin "6") (pinfunction "6_6") (pintype "passive"))
    )
    (net (code "65") (name "unconnected-(JP7-Pad8)") (class "Default")
      (node (ref "JP7") (pin "8") (pinfunction "8_8") (pintype "passive"))
    )
    (net (code "66") (name "unconnected-(T2-C{slash}-Pad4)") (class "Default")
      (node (ref "T2") (pin "4") (pinfunction "C/_4") (pintype "passive"))
    )
  )
)
